# Mis_-_ICSP_conector.net
KiCad netlist of a schematic drawn in Altium Designer
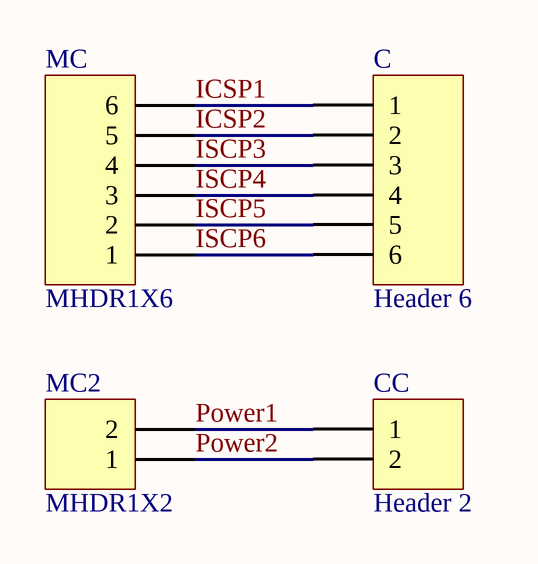
[diagram p0: Mis - ICSP conector.SchDoc]

(export (version "E")
  (design (tool "Eeschema 10.0.6"))
  (components
    (comp (ref "C")
      (value "Header 6")
      (footprint "HDR1X6")
      (description "Header, 6-Pin")
      (fields (field (name "PUBLISHER") "Altium Limited"))
      (libsource (lib "Miscellaneous Connectors") (part "Header 6"))
    )
    (comp (ref "CC")
      (value "Header 2")
      (footprint "HDR1X2")
      (description "Header, 2-Pin")
      (fields (field (name "PUBLISHER") "Altium Limited"))
      (libsource (lib "Miscellaneous Connectors") (part "Header 2"))
    )
    (comp (ref "MC")
      (value "MHDR1X6")
      (footprint "MHDR1X6")
      (description "Header, 6-Pin")
      (fields (field (name "PUBLISHER") "Altium Limited"))
      (libsource (lib "Miscellaneous Connectors") (part "MHDR1X6"))
    )
    (comp (ref "MC2")
      (value "MHDR1X2")
      (footprint "MHDR1X2")
      (description "Header, 2-Pin")
      (fields (field (name "PUBLISHER") "Altium Limited"))
      (libsource (lib "Miscellaneous Connectors") (part "MHDR1X2"))
    )
  )
  (nets
    (net (code "1") (name "/ICSP1") (class "Default")
      (node (ref "C") (pin "1") (pinfunction "1_1") (pintype "passive"))
      (node (ref "MC") (pin "6") (pinfunction "6_6") (pintype "passive"))
    )
    (net (code "2") (name "/ICSP2") (class "Default")
      (node (ref "C") (pin "2") (pinfunction "2_2") (pintype "passive"))
      (node (ref "MC") (pin "5") (pinfunction "5_5") (pintype "passive"))
    )
    (net (code "3") (name "/ISCP3") (class "Default")
      (node (ref "C") (pin "3") (pinfunction "3_3") (pintype "passive"))
      (node (ref "MC") (pin "4") (pinfunction "4_4") (pintype "passive"))
    )
    (net (code "4") (name "/ISCP4") (class "Default")
      (node (ref "C") (pin "4") (pinfunction "4_4") (pintype "passive"))
      (node (ref "MC") (pin "3") (pinfunction "3_3") (pintype "passive"))
    )
    (net (code "5") (name "/ISCP5") (class "Default")
      (node (ref "C") (pin "5") (pinfunction "5_5") (pintype "passive"))
      (node (ref "MC") (pin "2") (pinfunction "2_2") (pintype "passive"))
    )
    (net (code "6") (name "/ISCP6") (class "Default")
      (node (ref "C") (pin "6") (pinfunction "6_6") (pintype "passive"))
      (node (ref "MC") (pin "1") (pinfunction "1_1") (pintype "passive"))
    )
    (net (code "7") (name "/Power1") (class "Default")
      (node (ref "CC") (pin "1") (pinfunction "1_1") (pintype "passive"))
      (node (ref "MC2") (pin "2") (pinfunction "2_2") (pintype "passive"))
    )
    (net (code "8") (name "/Power2") (class "Default")
      (node (ref "CC") (pin "2") (pinfunction "2_2") (pintype "passive"))
      (node (ref "MC2") (pin "1") (pinfunction "1_1") (pintype "passive"))
    )
  )
)
